# picoBuck.net
KiCad netlist of a schematic drawn in EAGLE
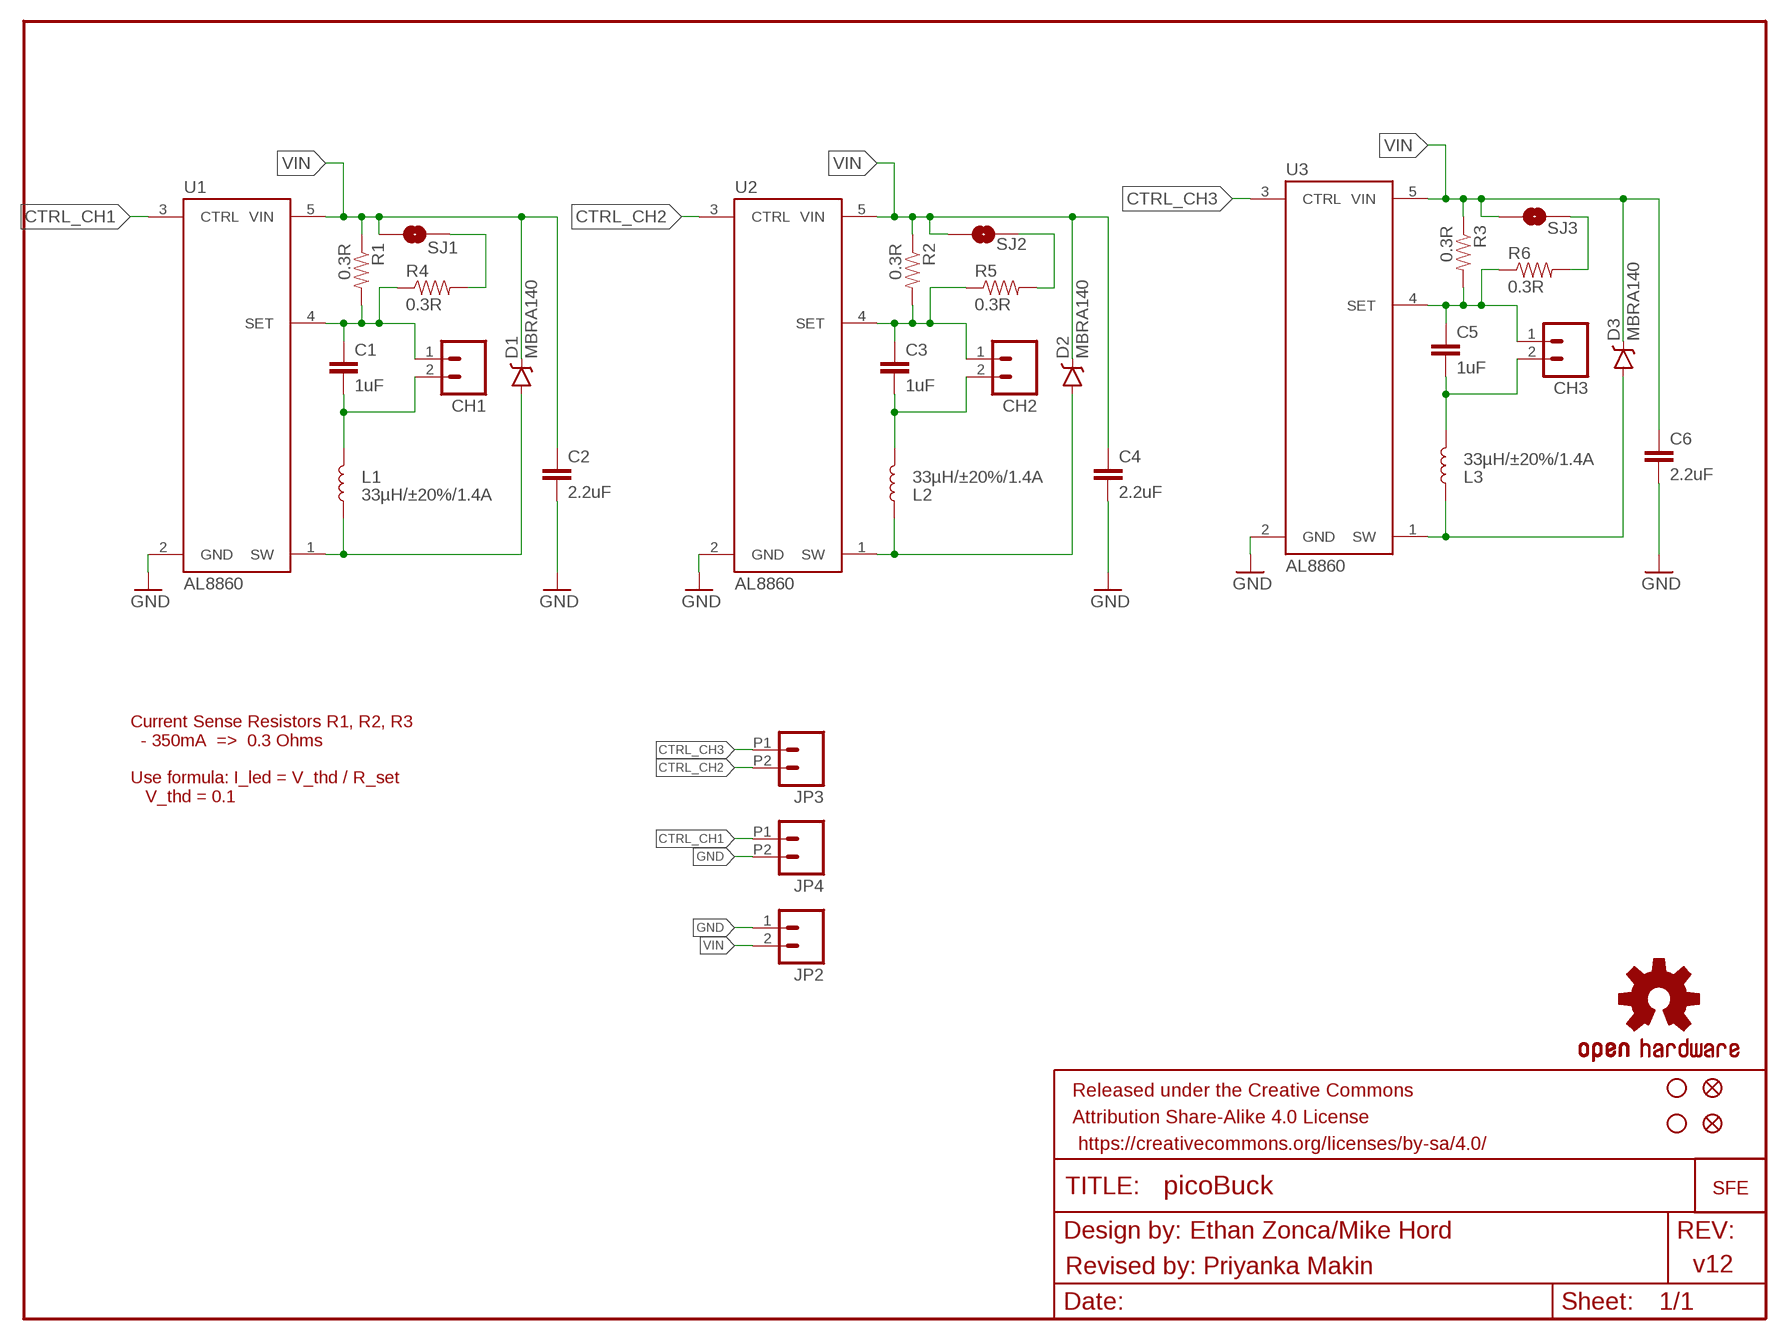
[diagram p0: schematic, sheet 1]

(export (version "E")
  (design (tool "Eeschema 10.0.6"))
  (components
    (comp (ref "C1")
      (value "1uF")
      (footprint "eagle-import:0805")
      (libsource (lib "eagle-import") (part "1.0UF-25V-+80/-20(0805)"))
    )
    (comp (ref "C2")
      (value "2.2uF")
      (footprint "eagle-import:0805")
      (libsource (lib "eagle-import") (part "2.2UF-25V-+80/-20(0805)"))
    )
    (comp (ref "C3")
      (value "1uF")
      (footprint "eagle-import:0805")
      (libsource (lib "eagle-import") (part "1.0UF-25V-+80/-20(0805)"))
    )
    (comp (ref "C4")
      (value "2.2uF")
      (footprint "eagle-import:0805")
      (libsource (lib "eagle-import") (part "2.2UF-25V-+80/-20(0805)"))
    )
    (comp (ref "C5")
      (value "1uF")
      (footprint "eagle-import:0805")
      (libsource (lib "eagle-import") (part "1.0UF-25V-+80/-20(0805)"))
    )
    (comp (ref "C6")
      (value "2.2uF")
      (footprint "eagle-import:0805")
      (libsource (lib "eagle-import") (part "2.2UF-25V-+80/-20(0805)"))
    )
    (comp (ref "CH1")
      (value "CONN_023.5MM_LOCK")
      (footprint "eagle-import:SCREWTERMINAL-3.5MM-2_LOCK")
      (libsource (lib "eagle-import") (part "CONN_023.5MM_LOCK"))
    )
    (comp (ref "CH2")
      (value "CONN_023.5MM_LOCK")
      (footprint "eagle-import:SCREWTERMINAL-3.5MM-2_LOCK")
      (libsource (lib "eagle-import") (part "CONN_023.5MM_LOCK"))
    )
    (comp (ref "CH3")
      (value "CONN_023.5MM_LOCK")
      (footprint "eagle-import:SCREWTERMINAL-3.5MM-2_LOCK")
      (libsource (lib "eagle-import") (part "CONN_023.5MM_LOCK"))
    )
    (comp (ref "D1")
      (value "MBRA140")
      (footprint "eagle-import:SMA-DIODE")
      (libsource (lib "eagle-import") (part "DIODE-SCHOTTKY-MBRA140"))
    )
    (comp (ref "D2")
      (value "MBRA140")
      (footprint "eagle-import:SMA-DIODE")
      (libsource (lib "eagle-import") (part "DIODE-SCHOTTKY-MBRA140"))
    )
    (comp (ref "D3")
      (value "MBRA140")
      (footprint "eagle-import:SMA-DIODE")
      (libsource (lib "eagle-import") (part "DIODE-SCHOTTKY-MBRA140"))
    )
    (comp (ref "FID1")
      (value "FIDUCIALUFIDUCIAL")
      (footprint "eagle-import:MICRO-FIDUCIAL")
      (libsource (lib "eagle-import") (part "FIDUCIALUFIDUCIAL"))
    )
    (comp (ref "FID2")
      (value "FIDUCIALUFIDUCIAL")
      (footprint "eagle-import:MICRO-FIDUCIAL")
      (libsource (lib "eagle-import") (part "FIDUCIALUFIDUCIAL"))
    )
    (comp (ref "FRAME1")
      (value "FRAME-LETTER")
      (footprint "eagle-import:CREATIVE_COMMONS")
      (libsource (lib "eagle-import") (part "FRAME-LETTER"))
    )
    (comp (ref "JP2")
      (value "CONN_023.5MM_LOCK")
      (footprint "eagle-import:SCREWTERMINAL-3.5MM-2_LOCK")
      (libsource (lib "eagle-import") (part "CONN_023.5MM_LOCK"))
    )
    (comp (ref "JP3")
      (value "M022.54MM_SCREWTERM")
      (footprint "eagle-import:1X02_2.54_SCREWTERM@1")
      (libsource (lib "eagle-import") (part "M022.54MM_SCREWTERM"))
    )
    (comp (ref "JP4")
      (value "M022.54MM_SCREWTERM")
      (footprint "eagle-import:1X02_2.54_SCREWTERM@1")
      (libsource (lib "eagle-import") (part "M022.54MM_SCREWTERM"))
    )
    (comp (ref "L1")
      (value "33µH/±20%/1.4A")
      (footprint "eagle-import:SRN6045")
      (libsource (lib "eagle-import") (part "INDUCTOR-SRN6045-33UH"))
    )
    (comp (ref "L2")
      (value "33µH/±20%/1.4A")
      (footprint "eagle-import:SRN6045")
      (libsource (lib "eagle-import") (part "INDUCTOR-SRN6045-33UH"))
    )
    (comp (ref "L3")
      (value "33µH/±20%/1.4A")
      (footprint "eagle-import:SRN6045")
      (libsource (lib "eagle-import") (part "INDUCTOR-SRN6045-33UH"))
    )
    (comp (ref "LOGO1")
      (value "OSHW-LOGOS")
      (footprint "eagle-import:OSHW-LOGO-S")
      (libsource (lib "eagle-import") (part "OSHW-LOGOS"))
    )
    (comp (ref "LOGO2")
      (value "LOGO-SFENEW")
      (footprint "eagle-import:SFE-NEW-WEBLOGO")
      (libsource (lib "eagle-import") (part "LOGO-SFENEW"))
    )
    (comp (ref "R1")
      (value "0.3R")
      (footprint "eagle-import:0805")
      (libsource (lib "eagle-import") (part "0.3OHM-1/8W-1%(0805)"))
    )
    (comp (ref "R2")
      (value "0.3R")
      (footprint "eagle-import:0805")
      (libsource (lib "eagle-import") (part "0.3OHM-1/8W-1%(0805)"))
    )
    (comp (ref "R3")
      (value "0.3R")
      (footprint "eagle-import:0805")
      (libsource (lib "eagle-import") (part "0.3OHM-1/8W-1%(0805)"))
    )
    (comp (ref "R4")
      (value "0.3R")
      (footprint "eagle-import:0805")
      (libsource (lib "eagle-import") (part "0.3OHM-1/8W-1%(0805)"))
    )
    (comp (ref "R5")
      (value "0.3R")
      (footprint "eagle-import:0805")
      (libsource (lib "eagle-import") (part "0.3OHM-1/8W-1%(0805)"))
    )
    (comp (ref "R6")
      (value "0.3R")
      (footprint "eagle-import:0805")
      (libsource (lib "eagle-import") (part "0.3OHM-1/8W-1%(0805)"))
    )
    (comp (ref "SJ1")
      (value "JUMPER-SMT_2_NO_NO-SILK")
      (footprint "eagle-import:SMT-JUMPER_2_NO_NO-SILK")
      (libsource (lib "eagle-import") (part "JUMPER-SMT_2_NO_NO-SILK"))
    )
    (comp (ref "SJ2")
      (value "JUMPER-SMT_2_NO_NO-SILK")
      (footprint "eagle-import:SMT-JUMPER_2_NO_NO-SILK")
      (libsource (lib "eagle-import") (part "JUMPER-SMT_2_NO_NO-SILK"))
    )
    (comp (ref "SJ3")
      (value "JUMPER-SMT_2_NO_NO-SILK")
      (footprint "eagle-import:SMT-JUMPER_2_NO_NO-SILK")
      (libsource (lib "eagle-import") (part "JUMPER-SMT_2_NO_NO-SILK"))
    )
    (comp (ref "STANDOFF1")
      (value "STAND-OFF")
      (footprint "eagle-import:STAND-OFF")
      (libsource (lib "eagle-import") (part "STAND-OFF"))
    )
    (comp (ref "STANDOFF2")
      (value "STAND-OFF")
      (footprint "eagle-import:STAND-OFF")
      (libsource (lib "eagle-import") (part "STAND-OFF"))
    )
    (comp (ref "U1")
      (value "AL8860")
      (footprint "eagle-import:SOT23-5")
      (libsource (lib "eagle-import") (part "AL8860SOT23"))
    )
    (comp (ref "U2")
      (value "AL8860")
      (footprint "eagle-import:SOT23-5")
      (libsource (lib "eagle-import") (part "AL8860SOT23"))
    )
    (comp (ref "U3")
      (value "AL8860")
      (footprint "eagle-import:SOT23-5")
      (libsource (lib "eagle-import") (part "AL8860SOT23"))
    )
  )
  (nets
    (net (code "1") (name "CTRL_CH1") (class "Default")
      (node (ref "JP4") (pin "P1") (pinfunction "1_P1") (pintype "passive"))
      (node (ref "U1") (pin "3") (pinfunction "CTRL_3") (pintype "bidirectional"))
    )
    (net (code "2") (name "CTRL_CH2") (class "Default")
      (node (ref "JP3") (pin "P2") (pinfunction "2_P2") (pintype "passive"))
      (node (ref "U2") (pin "3") (pinfunction "CTRL_3") (pintype "bidirectional"))
    )
    (net (code "3") (name "CTRL_CH3") (class "Default")
      (node (ref "JP3") (pin "P1") (pinfunction "1_P1") (pintype "passive"))
      (node (ref "U3") (pin "3") (pinfunction "CTRL_3") (pintype "bidirectional"))
    )
    (net (code "4") (name "GND") (class "Default")
      (node (ref "C2") (pin "2") (pinfunction "2_2") (pintype "passive"))
      (node (ref "C4") (pin "2") (pinfunction "2_2") (pintype "passive"))
      (node (ref "C6") (pin "2") (pinfunction "2_2") (pintype "passive"))
      (node (ref "JP2") (pin "1") (pinfunction "1_1") (pintype "passive"))
      (node (ref "JP4") (pin "P2") (pinfunction "2_P2") (pintype "passive"))
      (node (ref "U1") (pin "2") (pinfunction "GND_2") (pintype "bidirectional"))
      (node (ref "U2") (pin "2") (pinfunction "GND_2") (pintype "bidirectional"))
      (node (ref "U3") (pin "2") (pinfunction "GND_2") (pintype "bidirectional"))
    )
    (net (code "5") (name "Net-(C1-Pad2)") (class "Default")
      (node (ref "C1") (pin "2") (pinfunction "2_2") (pintype "passive"))
      (node (ref "CH1") (pin "2") (pinfunction "2_2") (pintype "passive"))
      (node (ref "L1") (pin "2") (pinfunction "2_2") (pintype "passive"))
    )
    (net (code "6") (name "Net-(C3-Pad2)") (class "Default")
      (node (ref "C3") (pin "2") (pinfunction "2_2") (pintype "passive"))
      (node (ref "CH2") (pin "2") (pinfunction "2_2") (pintype "passive"))
      (node (ref "L2") (pin "2") (pinfunction "2_2") (pintype "passive"))
    )
    (net (code "7") (name "Net-(C5-Pad2)") (class "Default")
      (node (ref "C5") (pin "2") (pinfunction "2_2") (pintype "passive"))
      (node (ref "CH3") (pin "2") (pinfunction "2_2") (pintype "passive"))
      (node (ref "L3") (pin "2") (pinfunction "2_2") (pintype "passive"))
    )
    (net (code "8") (name "Net-(R4-Pad2)") (class "Default")
      (node (ref "R4") (pin "2") (pinfunction "2_2") (pintype "passive"))
      (node (ref "SJ1") (pin "2") (pinfunction "2_2") (pintype "passive"))
    )
    (net (code "9") (name "Net-(R5-Pad2)") (class "Default")
      (node (ref "R5") (pin "2") (pinfunction "2_2") (pintype "passive"))
      (node (ref "SJ2") (pin "2") (pinfunction "2_2") (pintype "passive"))
    )
    (net (code "10") (name "Net-(R6-Pad2)") (class "Default")
      (node (ref "R6") (pin "2") (pinfunction "2_2") (pintype "passive"))
      (node (ref "SJ3") (pin "2") (pinfunction "2_2") (pintype "passive"))
    )
    (net (code "11") (name "Net-(U1-SET)") (class "Default")
      (node (ref "C1") (pin "1") (pinfunction "1_1") (pintype "passive"))
      (node (ref "CH1") (pin "1") (pinfunction "1_1") (pintype "passive"))
      (node (ref "R1") (pin "2") (pinfunction "2_2") (pintype "passive"))
      (node (ref "R4") (pin "1") (pinfunction "1_1") (pintype "passive"))
      (node (ref "U1") (pin "4") (pinfunction "SET_4") (pintype "bidirectional"))
    )
    (net (code "12") (name "Net-(U1-SW)") (class "Default")
      (node (ref "D1") (pin "A") (pinfunction "A_A") (pintype "passive"))
      (node (ref "L1") (pin "1") (pinfunction "1_1") (pintype "passive"))
      (node (ref "U1") (pin "1") (pinfunction "SW_1") (pintype "bidirectional"))
    )
    (net (code "13") (name "Net-(U2-SET)") (class "Default")
      (node (ref "C3") (pin "1") (pinfunction "1_1") (pintype "passive"))
      (node (ref "CH2") (pin "1") (pinfunction "1_1") (pintype "passive"))
      (node (ref "R2") (pin "2") (pinfunction "2_2") (pintype "passive"))
      (node (ref "R5") (pin "1") (pinfunction "1_1") (pintype "passive"))
      (node (ref "U2") (pin "4") (pinfunction "SET_4") (pintype "bidirectional"))
    )
    (net (code "14") (name "Net-(U2-SW)") (class "Default")
      (node (ref "D2") (pin "A") (pinfunction "A_A") (pintype "passive"))
      (node (ref "L2") (pin "1") (pinfunction "1_1") (pintype "passive"))
      (node (ref "U2") (pin "1") (pinfunction "SW_1") (pintype "bidirectional"))
    )
    (net (code "15") (name "Net-(U3-SET)") (class "Default")
      (node (ref "C5") (pin "1") (pinfunction "1_1") (pintype "passive"))
      (node (ref "CH3") (pin "1") (pinfunction "1_1") (pintype "passive"))
      (node (ref "R3") (pin "2") (pinfunction "2_2") (pintype "passive"))
      (node (ref "R6") (pin "1") (pinfunction "1_1") (pintype "passive"))
      (node (ref "U3") (pin "4") (pinfunction "SET_4") (pintype "bidirectional"))
    )
    (net (code "16") (name "Net-(U3-SW)") (class "Default")
      (node (ref "D3") (pin "A") (pinfunction "A_A") (pintype "passive"))
      (node (ref "L3") (pin "1") (pinfunction "1_1") (pintype "passive"))
      (node (ref "U3") (pin "1") (pinfunction "SW_1") (pintype "bidirectional"))
    )
    (net (code "17") (name "VIN") (class "Default")
      (node (ref "C2") (pin "1") (pinfunction "1_1") (pintype "passive"))
      (node (ref "C4") (pin "1") (pinfunction "1_1") (pintype "passive"))
      (node (ref "C6") (pin "1") (pinfunction "1_1") (pintype "passive"))
      (node (ref "D1") (pin "C") (pinfunction "C_C") (pintype "passive"))
      (node (ref "D2") (pin "C") (pinfunction "C_C") (pintype "passive"))
      (node (ref "D3") (pin "C") (pinfunction "C_C") (pintype "passive"))
      (node (ref "JP2") (pin "2") (pinfunction "2_2") (pintype "passive"))
      (node (ref "R1") (pin "1") (pinfunction "1_1") (pintype "passive"))
      (node (ref "R2") (pin "1") (pinfunction "1_1") (pintype "passive"))
      (node (ref "R3") (pin "1") (pinfunction "1_1") (pintype "passive"))
      (node (ref "SJ1") (pin "1") (pinfunction "1_1") (pintype "passive"))
      (node (ref "SJ2") (pin "1") (pinfunction "1_1") (pintype "passive"))
      (node (ref "SJ3") (pin "1") (pinfunction "1_1") (pintype "passive"))
      (node (ref "U1") (pin "5") (pinfunction "VIN_5") (pintype "bidirectional"))
      (node (ref "U2") (pin "5") (pinfunction "VIN_5") (pintype "bidirectional"))
      (node (ref "U3") (pin "5") (pinfunction "VIN_5") (pintype "bidirectional"))
    )
  )
)
